# preamp-buffer-supreme-v2.net
KiCad netlist of a schematic drawn in EAGLE
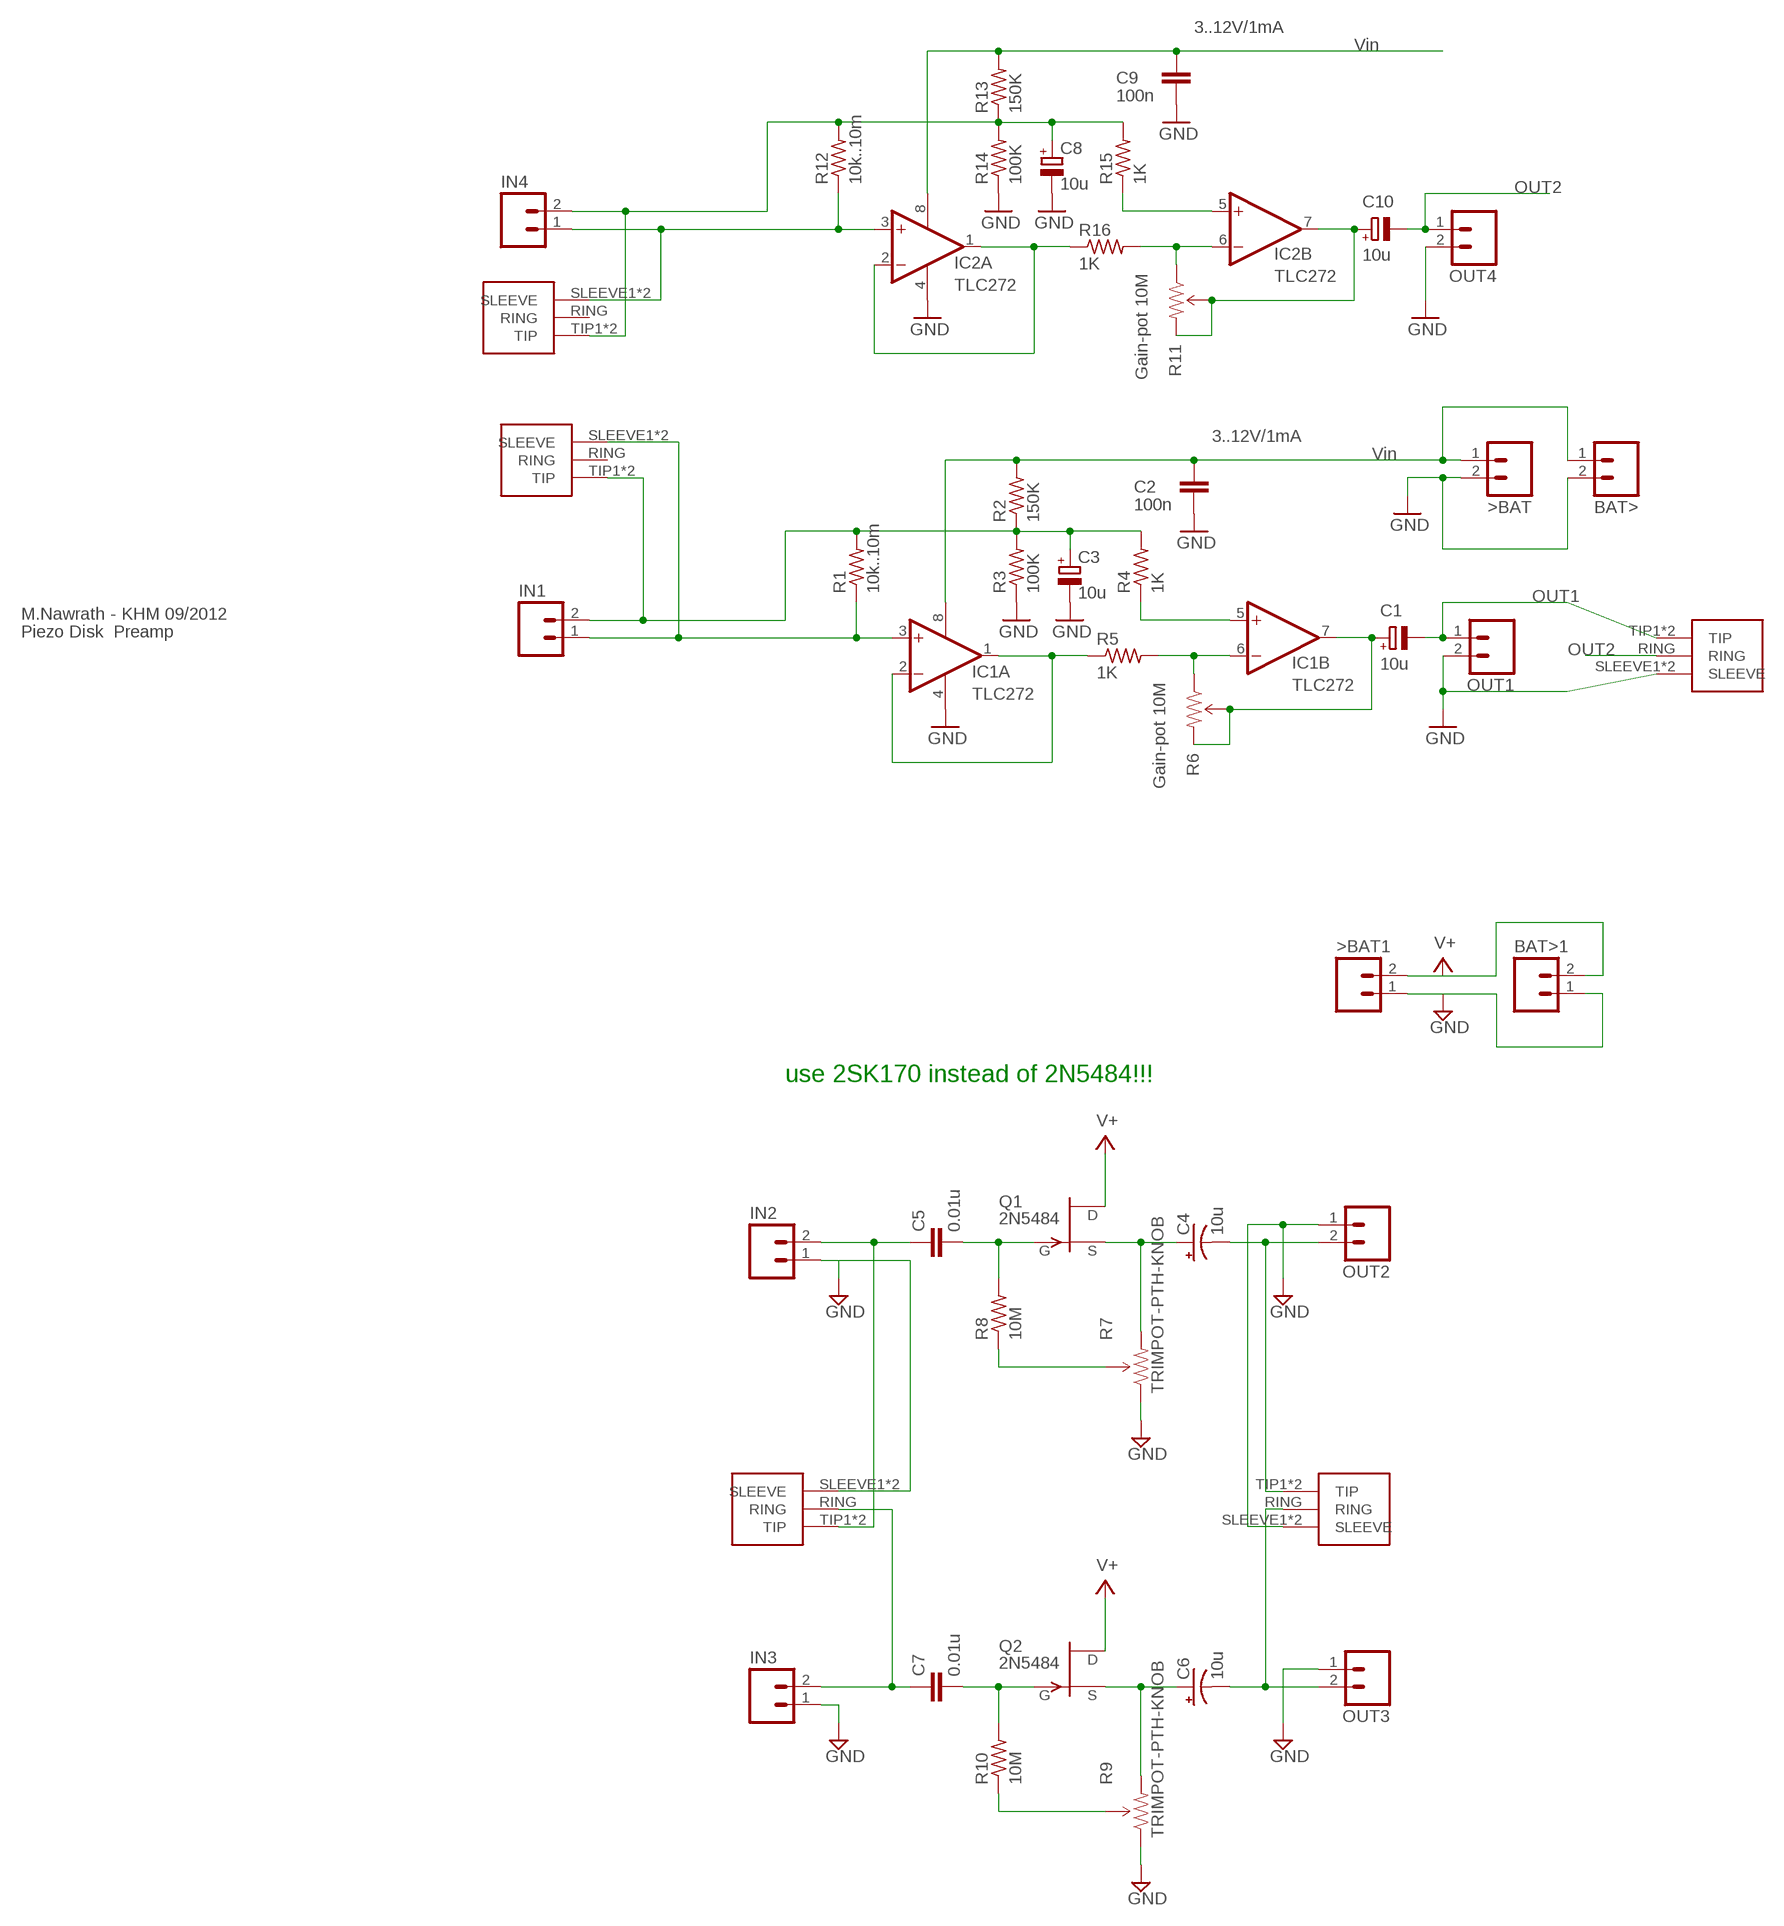
[diagram p0: schematic, sheet 1]

(export (version "E")
  (design (tool "Eeschema 10.0.6"))
  (components
    (comp (ref ">BAT")
      (value "M02LOCK")
      (footprint "eagle-import:1X02_LOCK")
      (libsource (lib "eagle-import") (part "M02LOCK"))
    )
    (comp (ref ">BAT1")
      (value "M02PTH")
      (footprint "eagle-import:1X02")
      (libsource (lib "eagle-import") (part "M02PTH"))
    )
    (comp (ref "BAT>")
      (value "M02LOCK")
      (footprint "eagle-import:1X02_LOCK")
      (libsource (lib "eagle-import") (part "M02LOCK"))
    )
    (comp (ref "BAT>1")
      (value "M02PTH")
      (footprint "eagle-import:1X02")
      (libsource (lib "eagle-import") (part "M02PTH"))
    )
    (comp (ref "C1")
      (value "10u")
      (footprint "eagle-import:E2,5-5")
      (libsource (lib "eagle-import") (part "CPOL-EUE2.5-5"))
    )
    (comp (ref "C2")
      (value "100n")
      (footprint "eagle-import:C025-025X050")
      (libsource (lib "eagle-import") (part "C-EU025-025X050"))
    )
    (comp (ref "C3")
      (value "10u")
      (footprint "eagle-import:E2,5-5")
      (libsource (lib "eagle-import") (part "CPOL-EUE2.5-5"))
    )
    (comp (ref "C4")
      (value "10u")
      (footprint "eagle-import:CPOL-RADIAL-10UF-25V")
      (libsource (lib "eagle-import") (part "CAP_POLPTH2"))
    )
    (comp (ref "C5")
      (value "0.01u")
      (footprint "eagle-import:C5B3")
      (libsource (lib "eagle-import") (part "C5/3"))
    )
    (comp (ref "C6")
      (value "10u")
      (footprint "eagle-import:CPOL-RADIAL-10UF-25V")
      (libsource (lib "eagle-import") (part "CAP_POLPTH2"))
    )
    (comp (ref "C7")
      (value "0.01u")
      (footprint "eagle-import:C5B3")
      (libsource (lib "eagle-import") (part "C5/3"))
    )
    (comp (ref "C8")
      (value "10u")
      (footprint "eagle-import:E2,5-5")
      (libsource (lib "eagle-import") (part "CPOL-EUE2.5-5"))
    )
    (comp (ref "C9")
      (value "100n")
      (footprint "eagle-import:C025-025X050")
      (libsource (lib "eagle-import") (part "C-EU025-025X050"))
    )
    (comp (ref "C10")
      (value "10u")
      (footprint "eagle-import:E2,5-5")
      (libsource (lib "eagle-import") (part "CPOL-EUE2.5-5"))
    )
    (comp (ref "IC1")
      (value "TLC272")
      (footprint "eagle-import:DIL08")
      (libsource (lib "eagle-import") (part "TLC272P"))
    )
    (comp (ref "IC2")
      (value "TLC272")
      (footprint "eagle-import:DIL08")
      (libsource (lib "eagle-import") (part "TLC272P"))
    )
    (comp (ref "IN1")
      (value "M02LOCK")
      (footprint "eagle-import:1X02_LOCK")
      (libsource (lib "eagle-import") (part "M02LOCK"))
    )
    (comp (ref "IN2")
      (value "M02LOCK")
      (footprint "eagle-import:1X02_LOCK")
      (libsource (lib "eagle-import") (part "M02LOCK"))
    )
    (comp (ref "IN3")
      (value "M02LOCK")
      (footprint "eagle-import:1X02_LOCK")
      (libsource (lib "eagle-import") (part "M02LOCK"))
    )
    (comp (ref "IN4")
      (value "M02LOCK")
      (footprint "eagle-import:1X02_LOCK")
      (libsource (lib "eagle-import") (part "M02LOCK"))
    )
    (comp (ref "OUT1")
      (value "M02LOCK")
      (footprint "eagle-import:1X02_LOCK")
      (libsource (lib "eagle-import") (part "M02LOCK"))
    )
    (comp (ref "OUT1-TRS")
      (value "1/8\"-F-STEREO-PCB")
      (footprint "eagle-import:1_8_-F-STEREO-PCB")
      (libsource (lib "eagle-import") (part "1/8{dblquote}-F-STEREO-PCB"))
    )
    (comp (ref "OUT2")
      (value "M02LOCK")
      (footprint "eagle-import:1X02_LOCK")
      (libsource (lib "eagle-import") (part "M02LOCK"))
    )
    (comp (ref "OUT3")
      (value "M02LOCK")
      (footprint "eagle-import:1X02_LOCK")
      (libsource (lib "eagle-import") (part "M02LOCK"))
    )
    (comp (ref "OUT4")
      (value "M02LOCK")
      (footprint "eagle-import:1X02_LOCK")
      (libsource (lib "eagle-import") (part "M02LOCK"))
    )
    (comp (ref "Q1")
      (value "2N5484")
      (footprint "eagle-import:TO92-")
      (libsource (lib "eagle-import") (part "?5482N4"))
    )
    (comp (ref "Q2")
      (value "2N5484")
      (footprint "eagle-import:TO92-")
      (libsource (lib "eagle-import") (part "?5482N4"))
    )
    (comp (ref "R1")
      (value "10k..10m")
      (footprint "eagle-import:0204V")
      (libsource (lib "eagle-import") (part "R-US_0204/2V"))
    )
    (comp (ref "R2")
      (value "150K")
      (footprint "eagle-import:0204V")
      (libsource (lib "eagle-import") (part "R-US_0204/2V"))
    )
    (comp (ref "R3")
      (value "100K")
      (footprint "eagle-import:0204V")
      (libsource (lib "eagle-import") (part "R-US_0204/2V"))
    )
    (comp (ref "R4")
      (value "1K")
      (footprint "eagle-import:0204V")
      (libsource (lib "eagle-import") (part "R-US_0204/2V"))
    )
    (comp (ref "R5")
      (value "1K")
      (footprint "eagle-import:0204V")
      (libsource (lib "eagle-import") (part "R-US_0204/2V"))
    )
    (comp (ref "R6")
      (value "Gain-pot 10M")
      (footprint "eagle-import:3386U")
      (libsource (lib "eagle-import") (part "TRIMPOT-PTH-KNOB"))
    )
    (comp (ref "R7")
      (value "TRIMPOT-PTH-KNOB")
      (footprint "eagle-import:3386U")
      (libsource (lib "eagle-import") (part "TRIMPOT-PTH-KNOB"))
    )
    (comp (ref "R8")
      (value "10M")
      (footprint "eagle-import:0204V")
      (libsource (lib "eagle-import") (part "R-US_0204/2V"))
    )
    (comp (ref "R9")
      (value "TRIMPOT-PTH-KNOB")
      (footprint "eagle-import:3386U")
      (libsource (lib "eagle-import") (part "TRIMPOT-PTH-KNOB"))
    )
    (comp (ref "R10")
      (value "10M")
      (footprint "eagle-import:0204V")
      (libsource (lib "eagle-import") (part "R-US_0204/2V"))
    )
    (comp (ref "R11")
      (value "Gain-pot 10M")
      (footprint "eagle-import:3386U")
      (libsource (lib "eagle-import") (part "TRIMPOT-PTH-KNOB"))
    )
    (comp (ref "R12")
      (value "10k..10m")
      (footprint "eagle-import:0204V")
      (libsource (lib "eagle-import") (part "R-US_0204/2V"))
    )
    (comp (ref "R13")
      (value "150K")
      (footprint "eagle-import:0204V")
      (libsource (lib "eagle-import") (part "R-US_0204/2V"))
    )
    (comp (ref "R14")
      (value "100K")
      (footprint "eagle-import:0204V")
      (libsource (lib "eagle-import") (part "R-US_0204/2V"))
    )
    (comp (ref "R15")
      (value "1K")
      (footprint "eagle-import:0204V")
      (libsource (lib "eagle-import") (part "R-US_0204/2V"))
    )
    (comp (ref "R16")
      (value "1K")
      (footprint "eagle-import:0204V")
      (libsource (lib "eagle-import") (part "R-US_0204/2V"))
    )
    (comp (ref "U$1")
      (value "1/8\"-F-STEREO-PCB")
      (footprint "eagle-import:1_8_-F-STEREO-PCB")
      (libsource (lib "eagle-import") (part "1/8{dblquote}-F-STEREO-PCB"))
    )
    (comp (ref "U$2")
      (value "1/8\"-F-STEREO-PCB")
      (footprint "eagle-import:1_8_-F-STEREO-PCB")
      (libsource (lib "eagle-import") (part "1/8{dblquote}-F-STEREO-PCB"))
    )
    (comp (ref "U$3")
      (value "1/8\"-F-STEREO-PCB")
      (footprint "eagle-import:1_8_-F-STEREO-PCB")
      (libsource (lib "eagle-import") (part "1/8{dblquote}-F-STEREO-PCB"))
    )
    (comp (ref "U$4")
      (value "1/8\"-F-STEREO-PCB")
      (footprint "eagle-import:1_8_-F-STEREO-PCB")
      (libsource (lib "eagle-import") (part "1/8{dblquote}-F-STEREO-PCB"))
    )
  )
  (nets
    (net (code "1") (name "/OUT2") (class "Default")
      (node (ref "C10") (pin "-") (pinfunction "-_-") (pintype "passive"))
      (node (ref "OUT1-TRS") (pin "RING") (pinfunction "RING_RING") (pintype "bidirectional"))
      (node (ref "OUT4") (pin "1") (pinfunction "1_1") (pintype "passive"))
    )
    (net (code "2") (name "/VIN") (class "Default")
      (node (ref ">BAT") (pin "1") (pinfunction "1_1") (pintype "passive"))
      (node (ref "BAT>") (pin "1") (pinfunction "1_1") (pintype "passive"))
      (node (ref "C2") (pin "2") (pinfunction "2_2") (pintype "passive"))
      (node (ref "C9") (pin "2") (pinfunction "2_2") (pintype "passive"))
      (node (ref "IC1") (pin "8") (pinfunction "V+_8") (pintype "power_in"))
      (node (ref "IC2") (pin "8") (pinfunction "V+_8") (pintype "power_in"))
      (node (ref "R13") (pin "2") (pinfunction "2_2") (pintype "passive"))
      (node (ref "R2") (pin "2") (pinfunction "2_2") (pintype "passive"))
    )
    (net (code "3") (name "GND") (class "Default")
      (node (ref ">BAT") (pin "2") (pinfunction "2_2") (pintype "passive"))
      (node (ref ">BAT1") (pin "1") (pinfunction "1_1") (pintype "passive"))
      (node (ref "BAT>") (pin "2") (pinfunction "2_2") (pintype "passive"))
      (node (ref "BAT>1") (pin "1") (pinfunction "1_1") (pintype "passive"))
      (node (ref "C2") (pin "1") (pinfunction "1_1") (pintype "passive"))
      (node (ref "C3") (pin "-") (pinfunction "-_-") (pintype "passive"))
      (node (ref "C8") (pin "-") (pinfunction "-_-") (pintype "passive"))
      (node (ref "C9") (pin "1") (pinfunction "1_1") (pintype "passive"))
      (node (ref "IC1") (pin "4") (pinfunction "V-_4") (pintype "power_in"))
      (node (ref "IC2") (pin "4") (pinfunction "V-_4") (pintype "power_in"))
      (node (ref "IN2") (pin "1") (pinfunction "1_1") (pintype "passive"))
      (node (ref "IN3") (pin "1") (pinfunction "1_1") (pintype "passive"))
      (node (ref "OUT1") (pin "2") (pinfunction "2_2") (pintype "passive"))
      (node (ref "OUT1-TRS") (pin "SLEEVE1") (pinfunction "SLEEVE_SLEEVE1") (pintype "bidirectional"))
      (node (ref "OUT1-TRS") (pin "SLEEVE2") (pinfunction "SLEEVE_SLEEVE2") (pintype "bidirectional"))
      (node (ref "OUT2") (pin "1") (pinfunction "1_1") (pintype "passive"))
      (node (ref "OUT3") (pin "1") (pinfunction "1_1") (pintype "passive"))
      (node (ref "OUT4") (pin "2") (pinfunction "2_2") (pintype "passive"))
      (node (ref "R14") (pin "1") (pinfunction "1_1") (pintype "passive"))
      (node (ref "R3") (pin "1") (pinfunction "1_1") (pintype "passive"))
      (node (ref "R7") (pin "1") (pinfunction "CCW_1") (pintype "passive"))
      (node (ref "R9") (pin "1") (pinfunction "CCW_1") (pintype "passive"))
      (node (ref "U$1") (pin "SLEEVE1") (pinfunction "SLEEVE_SLEEVE1") (pintype "bidirectional"))
      (node (ref "U$1") (pin "SLEEVE2") (pinfunction "SLEEVE_SLEEVE2") (pintype "bidirectional"))
      (node (ref "U$3") (pin "SLEEVE1") (pinfunction "SLEEVE_SLEEVE1") (pintype "bidirectional"))
      (node (ref "U$3") (pin "SLEEVE2") (pinfunction "SLEEVE_SLEEVE2") (pintype "bidirectional"))
    )
    (net (code "4") (name "Net-(C1-Pad-)") (class "Default")
      (node (ref "C1") (pin "-") (pinfunction "-_-") (pintype "passive"))
      (node (ref "OUT1") (pin "1") (pinfunction "1_1") (pintype "passive"))
      (node (ref "OUT1-TRS") (pin "TIP1") (pinfunction "TIP_TIP1") (pintype "bidirectional"))
      (node (ref "OUT1-TRS") (pin "TIP2") (pinfunction "TIP_TIP2") (pintype "bidirectional"))
    )
    (net (code "5") (name "Net-(C3-Pad+)") (class "Default")
      (node (ref "C3") (pin "+") (pinfunction "+_+") (pintype "passive"))
      (node (ref "IN1") (pin "2") (pinfunction "2_2") (pintype "passive"))
      (node (ref "R1") (pin "2") (pinfunction "2_2") (pintype "passive"))
      (node (ref "R2") (pin "1") (pinfunction "1_1") (pintype "passive"))
      (node (ref "R3") (pin "2") (pinfunction "2_2") (pintype "passive"))
      (node (ref "R4") (pin "2") (pinfunction "2_2") (pintype "passive"))
      (node (ref "U$2") (pin "TIP1") (pinfunction "TIP_TIP1") (pintype "bidirectional"))
      (node (ref "U$2") (pin "TIP2") (pinfunction "TIP_TIP2") (pintype "bidirectional"))
    )
    (net (code "6") (name "Net-(C4-+)") (class "Default")
      (node (ref "C4") (pin "1") (pinfunction "+_1") (pintype "passive"))
      (node (ref "Q1") (pin "2") (pinfunction "S_2") (pintype "passive"))
      (node (ref "R7") (pin "3") (pinfunction "CW_3") (pintype "passive"))
    )
    (net (code "7") (name "Net-(C4--)") (class "Default")
      (node (ref "C4") (pin "2") (pinfunction "-_2") (pintype "passive"))
      (node (ref "OUT2") (pin "2") (pinfunction "2_2") (pintype "passive"))
      (node (ref "U$1") (pin "TIP1") (pinfunction "TIP_TIP1") (pintype "bidirectional"))
      (node (ref "U$1") (pin "TIP2") (pinfunction "TIP_TIP2") (pintype "bidirectional"))
    )
    (net (code "8") (name "Net-(C5-Pad1)") (class "Default")
      (node (ref "C5") (pin "1") (pinfunction "1_1") (pintype "passive"))
      (node (ref "IN2") (pin "2") (pinfunction "2_2") (pintype "passive"))
      (node (ref "U$3") (pin "TIP1") (pinfunction "TIP_TIP1") (pintype "bidirectional"))
      (node (ref "U$3") (pin "TIP2") (pinfunction "TIP_TIP2") (pintype "bidirectional"))
    )
    (net (code "9") (name "Net-(C6-+)") (class "Default")
      (node (ref "C6") (pin "1") (pinfunction "+_1") (pintype "passive"))
      (node (ref "Q2") (pin "2") (pinfunction "S_2") (pintype "passive"))
      (node (ref "R9") (pin "3") (pinfunction "CW_3") (pintype "passive"))
    )
    (net (code "10") (name "Net-(C6--)") (class "Default")
      (node (ref "C6") (pin "2") (pinfunction "-_2") (pintype "passive"))
      (node (ref "OUT3") (pin "2") (pinfunction "2_2") (pintype "passive"))
      (node (ref "U$1") (pin "RING") (pinfunction "RING_RING") (pintype "bidirectional"))
    )
    (net (code "11") (name "Net-(C7-Pad1)") (class "Default")
      (node (ref "C7") (pin "1") (pinfunction "1_1") (pintype "passive"))
      (node (ref "IN3") (pin "2") (pinfunction "2_2") (pintype "passive"))
      (node (ref "U$3") (pin "RING") (pinfunction "RING_RING") (pintype "bidirectional"))
    )
    (net (code "12") (name "Net-(C8-Pad+)") (class "Default")
      (node (ref "C8") (pin "+") (pinfunction "+_+") (pintype "passive"))
      (node (ref "IN4") (pin "2") (pinfunction "2_2") (pintype "passive"))
      (node (ref "R12") (pin "2") (pinfunction "2_2") (pintype "passive"))
      (node (ref "R13") (pin "1") (pinfunction "1_1") (pintype "passive"))
      (node (ref "R14") (pin "2") (pinfunction "2_2") (pintype "passive"))
      (node (ref "R15") (pin "2") (pinfunction "2_2") (pintype "passive"))
      (node (ref "U$4") (pin "TIP1") (pinfunction "TIP_TIP1") (pintype "bidirectional"))
      (node (ref "U$4") (pin "TIP2") (pinfunction "TIP_TIP2") (pintype "bidirectional"))
    )
    (net (code "13") (name "Net-(IC1A-+IN)") (class "Default")
      (node (ref "IC1") (pin "3") (pinfunction "+IN_3") (pintype "input"))
      (node (ref "IN1") (pin "1") (pinfunction "1_1") (pintype "passive"))
      (node (ref "R1") (pin "1") (pinfunction "1_1") (pintype "passive"))
      (node (ref "U$2") (pin "SLEEVE1") (pinfunction "SLEEVE_SLEEVE1") (pintype "bidirectional"))
      (node (ref "U$2") (pin "SLEEVE2") (pinfunction "SLEEVE_SLEEVE2") (pintype "bidirectional"))
    )
    (net (code "14") (name "Net-(IC1A--IN)") (class "Default")
      (node (ref "IC1") (pin "1") (pinfunction "OUT_1") (pintype "output"))
      (node (ref "IC1") (pin "2") (pinfunction "-IN_2") (pintype "input"))
      (node (ref "R5") (pin "1") (pinfunction "1_1") (pintype "passive"))
    )
    (net (code "15") (name "Net-(IC1B-+IN)") (class "Default")
      (node (ref "IC1") (pin "5") (pinfunction "+IN_5") (pintype "input"))
      (node (ref "R4") (pin "1") (pinfunction "1_1") (pintype "passive"))
    )
    (net (code "16") (name "Net-(IC1B--IN)") (class "Default")
      (node (ref "IC1") (pin "6") (pinfunction "-IN_6") (pintype "input"))
      (node (ref "R5") (pin "2") (pinfunction "2_2") (pintype "passive"))
      (node (ref "R6") (pin "1") (pinfunction "CCW_1") (pintype "passive"))
    )
    (net (code "17") (name "Net-(IC1B-OUT)") (class "Default")
      (node (ref "C1") (pin "+") (pinfunction "+_+") (pintype "passive"))
      (node (ref "IC1") (pin "7") (pinfunction "OUT_7") (pintype "output"))
      (node (ref "R6") (pin "2") (pinfunction "WIPER_2") (pintype "passive"))
      (node (ref "R6") (pin "3") (pinfunction "CW_3") (pintype "passive"))
    )
    (net (code "18") (name "Net-(IC2A-+IN)") (class "Default")
      (node (ref "IC2") (pin "3") (pinfunction "+IN_3") (pintype "input"))
      (node (ref "IN4") (pin "1") (pinfunction "1_1") (pintype "passive"))
      (node (ref "R12") (pin "1") (pinfunction "1_1") (pintype "passive"))
      (node (ref "U$4") (pin "SLEEVE1") (pinfunction "SLEEVE_SLEEVE1") (pintype "bidirectional"))
      (node (ref "U$4") (pin "SLEEVE2") (pinfunction "SLEEVE_SLEEVE2") (pintype "bidirectional"))
    )
    (net (code "19") (name "Net-(IC2A--IN)") (class "Default")
      (node (ref "IC2") (pin "1") (pinfunction "OUT_1") (pintype "output"))
      (node (ref "IC2") (pin "2") (pinfunction "-IN_2") (pintype "input"))
      (node (ref "R16") (pin "1") (pinfunction "1_1") (pintype "passive"))
    )
    (net (code "20") (name "Net-(IC2B-+IN)") (class "Default")
      (node (ref "IC2") (pin "5") (pinfunction "+IN_5") (pintype "input"))
      (node (ref "R15") (pin "1") (pinfunction "1_1") (pintype "passive"))
    )
    (net (code "21") (name "Net-(IC2B--IN)") (class "Default")
      (node (ref "IC2") (pin "6") (pinfunction "-IN_6") (pintype "input"))
      (node (ref "R11") (pin "1") (pinfunction "CCW_1") (pintype "passive"))
      (node (ref "R16") (pin "2") (pinfunction "2_2") (pintype "passive"))
    )
    (net (code "22") (name "Net-(IC2B-OUT)") (class "Default")
      (node (ref "C10") (pin "+") (pinfunction "+_+") (pintype "passive"))
      (node (ref "IC2") (pin "7") (pinfunction "OUT_7") (pintype "output"))
      (node (ref "R11") (pin "2") (pinfunction "WIPER_2") (pintype "passive"))
      (node (ref "R11") (pin "3") (pinfunction "CW_3") (pintype "passive"))
    )
    (net (code "23") (name "Net-(Q1-G)") (class "Default")
      (node (ref "C5") (pin "2") (pinfunction "2_2") (pintype "passive"))
      (node (ref "Q1") (pin "1") (pinfunction "G_1") (pintype "passive"))
      (node (ref "R8") (pin "2") (pinfunction "2_2") (pintype "passive"))
    )
    (net (code "24") (name "Net-(Q2-G)") (class "Default")
      (node (ref "C7") (pin "2") (pinfunction "2_2") (pintype "passive"))
      (node (ref "Q2") (pin "1") (pinfunction "G_1") (pintype "passive"))
      (node (ref "R10") (pin "2") (pinfunction "2_2") (pintype "passive"))
    )
    (net (code "25") (name "Net-(R7-WIPER)") (class "Default")
      (node (ref "R7") (pin "2") (pinfunction "WIPER_2") (pintype "passive"))
      (node (ref "R8") (pin "1") (pinfunction "1_1") (pintype "passive"))
    )
    (net (code "26") (name "Net-(R9-WIPER)") (class "Default")
      (node (ref "R10") (pin "1") (pinfunction "1_1") (pintype "passive"))
      (node (ref "R9") (pin "2") (pinfunction "WIPER_2") (pintype "passive"))
    )
    (net (code "27") (name "V+") (class "Default")
      (node (ref ">BAT1") (pin "2") (pinfunction "2_2") (pintype "passive"))
      (node (ref "BAT>1") (pin "2") (pinfunction "2_2") (pintype "passive"))
      (node (ref "Q1") (pin "3") (pinfunction "D_3") (pintype "passive"))
      (node (ref "Q2") (pin "3") (pinfunction "D_3") (pintype "passive"))
    )
    (net (code "28") (name "unconnected-(U$2-PadRING)") (class "Default")
      (node (ref "U$2") (pin "RING") (pinfunction "RING_RING") (pintype "bidirectional"))
    )
    (net (code "29") (name "unconnected-(U$4-PadRING)") (class "Default")
      (node (ref "U$4") (pin "RING") (pinfunction "RING_RING") (pintype "bidirectional"))
    )
  )
)
